# connector_to_BMS_extension.net
KiCad netlist of a schematic drawn in Altium Designer
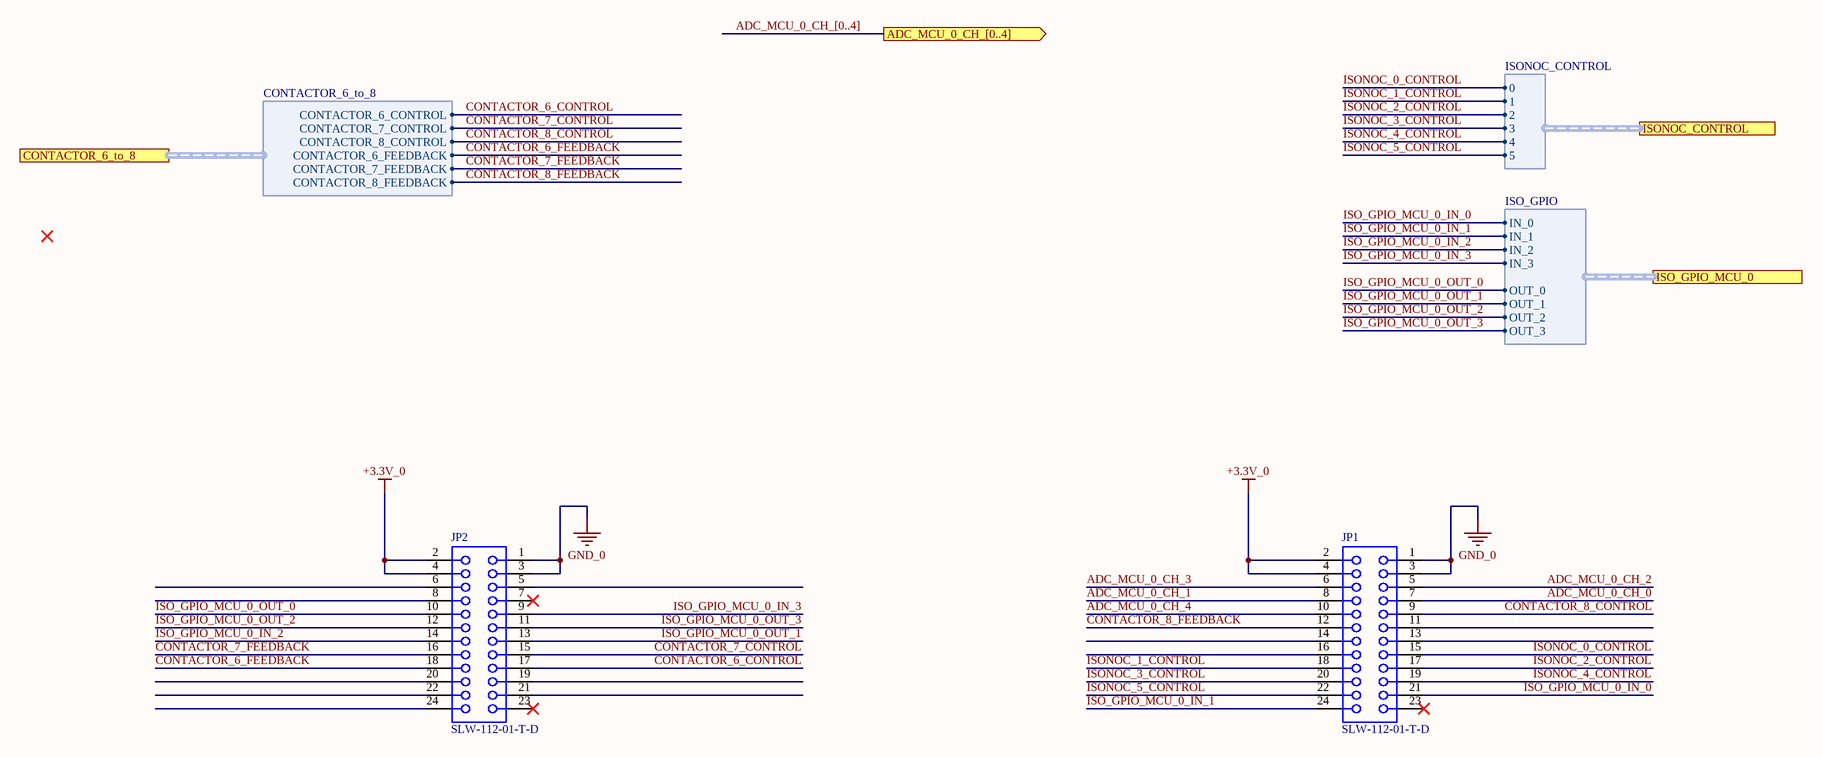
[diagram p0: connector_to_BMS_extension.SchDoc]

(export (version "E")
  (design (tool "Eeschema 10.0.6"))
  (components
    (comp (ref "JP1")
      (value "SLW-112-01-T-D")
      (footprint "SMTC-SLW-112-01-X-D")
      (fields (field (name "MANUFACTURER") "Samtec"))
      (libsource (lib "Altium Content Vault") (part "SMTC-SLW-112-01-X-D"))
    )
    (comp (ref "JP2")
      (value "SLW-112-01-T-D")
      (footprint "SMTC-SLW-112-01-X-D")
      (fields (field (name "MANUFACTURER") "Samtec"))
      (libsource (lib "Altium Content Vault") (part "SMTC-SLW-112-01-X-D"))
    )
  )
  (nets
    (net (code "4") (name "+3.3V_0") (class "Default")
      (node (ref "JP1") (pin "2") (pinfunction "2_2") (pintype "passive"))
      (node (ref "JP1") (pin "4") (pinfunction "4_4") (pintype "passive"))
      (node (ref "JP2") (pin "2") (pinfunction "2_2") (pintype "passive"))
      (node (ref "JP2") (pin "4") (pinfunction "4_4") (pintype "passive"))
    )
    (net (code "5") (name "/ADC_MCU_0_CH_0") (class "Default")
      (node (ref "JP1") (pin "7") (pinfunction "7_7") (pintype "passive"))
    )
    (net (code "6") (name "/ADC_MCU_0_CH_1") (class "Default")
      (node (ref "JP1") (pin "8") (pinfunction "8_8") (pintype "passive"))
    )
    (net (code "7") (name "/ADC_MCU_0_CH_2") (class "Default")
      (node (ref "JP1") (pin "5") (pinfunction "5_5") (pintype "passive"))
    )
    (net (code "8") (name "/ADC_MCU_0_CH_3") (class "Default")
      (node (ref "JP1") (pin "6") (pinfunction "6_6") (pintype "passive"))
    )
    (net (code "9") (name "/ADC_MCU_0_CH_4") (class "Default")
      (node (ref "JP1") (pin "10") (pinfunction "10_10") (pintype "passive"))
    )
    (net (code "11") (name "/CONTACTOR_6_CONTROL") (class "Default")
      (node (ref "JP2") (pin "17") (pinfunction "17_17") (pintype "passive"))
    )
    (net (code "12") (name "/CONTACTOR_6_FEEDBACK") (class "Default")
      (node (ref "JP2") (pin "18") (pinfunction "18_18") (pintype "passive"))
    )
    (net (code "13") (name "/CONTACTOR_7_CONTROL") (class "Default")
      (node (ref "JP2") (pin "15") (pinfunction "15_15") (pintype "passive"))
    )
    (net (code "14") (name "/CONTACTOR_7_FEEDBACK") (class "Default")
      (node (ref "JP2") (pin "16") (pinfunction "16_16") (pintype "passive"))
    )
    (net (code "15") (name "/CONTACTOR_8_CONTROL") (class "Default")
      (node (ref "JP1") (pin "9") (pinfunction "9_9") (pintype "passive"))
    )
    (net (code "16") (name "/CONTACTOR_8_FEEDBACK") (class "Default")
      (node (ref "JP1") (pin "12") (pinfunction "12_12") (pintype "passive"))
    )
    (net (code "17") (name "/ISONOC_0_CONTROL") (class "Default")
      (node (ref "JP1") (pin "15") (pinfunction "15_15") (pintype "passive"))
    )
    (net (code "18") (name "/ISONOC_1_CONTROL") (class "Default")
      (node (ref "JP1") (pin "18") (pinfunction "18_18") (pintype "passive"))
    )
    (net (code "19") (name "/ISONOC_2_CONTROL") (class "Default")
      (node (ref "JP1") (pin "17") (pinfunction "17_17") (pintype "passive"))
    )
    (net (code "20") (name "/ISONOC_3_CONTROL") (class "Default")
      (node (ref "JP1") (pin "20") (pinfunction "20_20") (pintype "passive"))
    )
    (net (code "21") (name "/ISONOC_4_CONTROL") (class "Default")
      (node (ref "JP1") (pin "19") (pinfunction "19_19") (pintype "passive"))
    )
    (net (code "22") (name "/ISONOC_5_CONTROL") (class "Default")
      (node (ref "JP1") (pin "22") (pinfunction "22_22") (pintype "passive"))
    )
    (net (code "23") (name "/ISO_GPIO_MCU_0_IN_0") (class "Default")
      (node (ref "JP1") (pin "21") (pinfunction "21_21") (pintype "passive"))
    )
    (net (code "24") (name "/ISO_GPIO_MCU_0_IN_1") (class "Default")
      (node (ref "JP1") (pin "24") (pinfunction "24_24") (pintype "passive"))
    )
    (net (code "25") (name "/ISO_GPIO_MCU_0_IN_2") (class "Default")
      (node (ref "JP2") (pin "14") (pinfunction "14_14") (pintype "passive"))
    )
    (net (code "26") (name "/ISO_GPIO_MCU_0_IN_3") (class "Default")
      (node (ref "JP2") (pin "9") (pinfunction "9_9") (pintype "passive"))
    )
    (net (code "27") (name "/ISO_GPIO_MCU_0_OUT_0") (class "Default")
      (node (ref "JP2") (pin "10") (pinfunction "10_10") (pintype "passive"))
    )
    (net (code "28") (name "/ISO_GPIO_MCU_0_OUT_1") (class "Default")
      (node (ref "JP2") (pin "13") (pinfunction "13_13") (pintype "passive"))
    )
    (net (code "29") (name "/ISO_GPIO_MCU_0_OUT_2") (class "Default")
      (node (ref "JP2") (pin "12") (pinfunction "12_12") (pintype "passive"))
    )
    (net (code "30") (name "/ISO_GPIO_MCU_0_OUT_3") (class "Default")
      (node (ref "JP2") (pin "11") (pinfunction "11_11") (pintype "passive"))
    )
    (net (code "34") (name "GND_0") (class "Default")
      (node (ref "JP1") (pin "1") (pinfunction "1_1") (pintype "passive"))
      (node (ref "JP1") (pin "3") (pinfunction "3_3") (pintype "passive"))
      (node (ref "JP2") (pin "1") (pinfunction "1_1") (pintype "passive"))
      (node (ref "JP2") (pin "3") (pinfunction "3_3") (pintype "passive"))
    )
    (net (code "35") (name "unconnected-(JP1-Pad11)") (class "Default")
      (node (ref "JP1") (pin "11") (pinfunction "11_11") (pintype "passive"))
    )
    (net (code "36") (name "unconnected-(JP1-Pad13)") (class "Default")
      (node (ref "JP1") (pin "13") (pinfunction "13_13") (pintype "passive"))
    )
    (net (code "37") (name "unconnected-(JP1-Pad14)") (class "Default")
      (node (ref "JP1") (pin "14") (pinfunction "14_14") (pintype "passive"))
    )
    (net (code "38") (name "unconnected-(JP1-Pad16)") (class "Default")
      (node (ref "JP1") (pin "16") (pinfunction "16_16") (pintype "passive"))
    )
    (net (code "39") (name "unconnected-(JP1-Pad23)") (class "Default")
      (node (ref "JP1") (pin "23") (pinfunction "23_23") (pintype "passive+no_connect"))
    )
    (net (code "40") (name "unconnected-(JP2-Pad5)") (class "Default")
      (node (ref "JP2") (pin "5") (pinfunction "5_5") (pintype "passive"))
    )
    (net (code "41") (name "unconnected-(JP2-Pad6)") (class "Default")
      (node (ref "JP2") (pin "6") (pinfunction "6_6") (pintype "passive"))
    )
    (net (code "42") (name "unconnected-(JP2-Pad7)") (class "Default")
      (node (ref "JP2") (pin "7") (pinfunction "7_7") (pintype "passive+no_connect"))
    )
    (net (code "43") (name "unconnected-(JP2-Pad8)") (class "Default")
      (node (ref "JP2") (pin "8") (pinfunction "8_8") (pintype "passive"))
    )
    (net (code "44") (name "unconnected-(JP2-Pad19)") (class "Default")
      (node (ref "JP2") (pin "19") (pinfunction "19_19") (pintype "passive"))
    )
    (net (code "45") (name "unconnected-(JP2-Pad20)") (class "Default")
      (node (ref "JP2") (pin "20") (pinfunction "20_20") (pintype "passive"))
    )
    (net (code "46") (name "unconnected-(JP2-Pad21)") (class "Default")
      (node (ref "JP2") (pin "21") (pinfunction "21_21") (pintype "passive"))
    )
    (net (code "47") (name "unconnected-(JP2-Pad22)") (class "Default")
      (node (ref "JP2") (pin "22") (pinfunction "22_22") (pintype "passive"))
    )
    (net (code "48") (name "unconnected-(JP2-Pad23)") (class "Default")
      (node (ref "JP2") (pin "23") (pinfunction "23_23") (pintype "passive+no_connect"))
    )
    (net (code "49") (name "unconnected-(JP2-Pad24)") (class "Default")
      (node (ref "JP2") (pin "24") (pinfunction "24_24") (pintype "passive"))
    )
  )
)
